# lora-rx.net
KiCad netlist of a schematic drawn in EAGLE
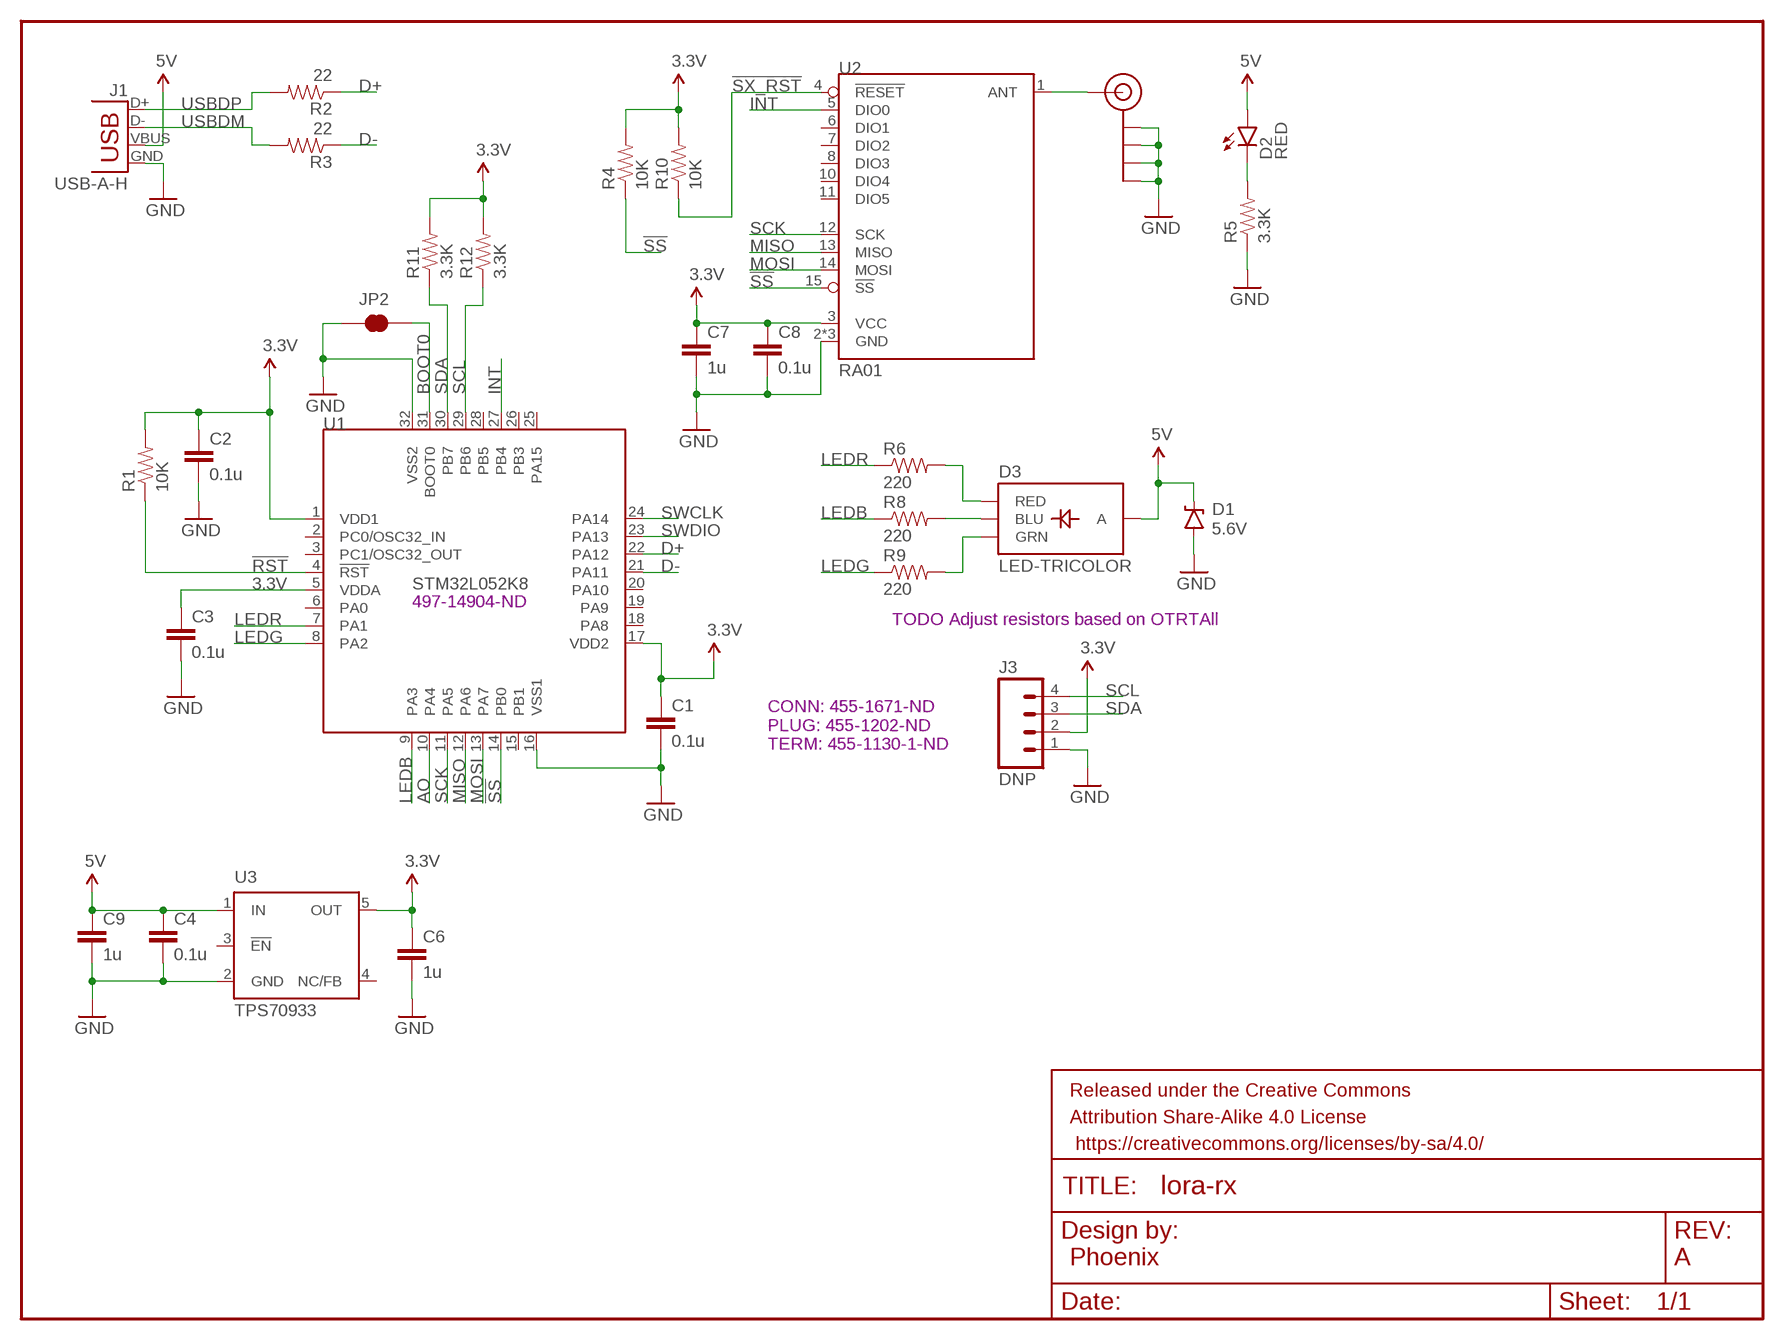
[diagram p0: schematic, sheet 1]

(export (version "E")
  (design (tool "Eeschema 10.0.6"))
  (components
    (comp (ref "C1")
      (value "0.1u")
      (footprint "eagle-import:0805")
      (libsource (lib "eagle-import") (part "CAP0805"))
    )
    (comp (ref "C2")
      (value "0.1u")
      (footprint "eagle-import:0805")
      (libsource (lib "eagle-import") (part "CAP0805"))
    )
    (comp (ref "C3")
      (value "0.1u")
      (footprint "eagle-import:0805")
      (libsource (lib "eagle-import") (part "CAP0805"))
    )
    (comp (ref "C4")
      (value "0.1u")
      (footprint "eagle-import:0805")
      (libsource (lib "eagle-import") (part "CAP0805"))
    )
    (comp (ref "C6")
      (value "1u")
      (footprint "eagle-import:0805")
      (libsource (lib "eagle-import") (part "CAP0805"))
    )
    (comp (ref "C7")
      (value "1u")
      (footprint "eagle-import:0805")
      (libsource (lib "eagle-import") (part "CAP0805"))
    )
    (comp (ref "C8")
      (value "0.1u")
      (footprint "eagle-import:0805")
      (libsource (lib "eagle-import") (part "CAP0805"))
    )
    (comp (ref "C9")
      (value "1u")
      (footprint "eagle-import:0805")
      (libsource (lib "eagle-import") (part "CAP0805"))
    )
    (comp (ref "D1")
      (value "5.6V")
      (footprint "eagle-import:SOD-323")
      (libsource (lib "eagle-import") (part "DIODE-ZENER5.6V"))
    )
    (comp (ref "D2")
      (value "RED")
      (footprint "eagle-import:LED-0603")
      (libsource (lib "eagle-import") (part "LED-RED0603"))
    )
    (comp (ref "D3")
      (value "LED-TRICOLOR")
      (footprint "eagle-import:LED-TRICOLOR-SMD")
      (libsource (lib "eagle-import") (part "LED-TRICOLOR"))
    )
    (comp (ref "FRAME1")
      (value "FRAME-LETTERNO_PACKAGE")
      (footprint "eagle-import:DUMMY")
      (fields (field (name "DESIGNER") "Nobody"))
      (libsource (lib "eagle-import") (part "FRAME-LETTERNO_PACKAGE"))
    )
    (comp (ref "J1")
      (value "USB-A-H")
      (footprint "eagle-import:USB-A-H")
      (libsource (lib "eagle-import") (part "USB-A-H"))
    )
    (comp (ref "J2")
      (value "SMA_EDGE")
      (footprint "eagle-import:SMA-EDGE")
      (libsource (lib "eagle-import") (part "SMA_EDGE"))
    )
    (comp (ref "J3")
      (value "DNP")
      (footprint "eagle-import:1X04-1.5MM_JST")
      (libsource (lib "eagle-import") (part "M04JST"))
    )
    (comp (ref "JP2")
      (value "JUMPER-SMT_2_NC_TRACE_NO-SILK")
      (footprint "eagle-import:SMT-JUMPER_2_NC_TRACE_NO-SILK")
      (libsource (lib "eagle-import") (part "JUMPER-SMT_2_NC_TRACE_NO-SILK"))
    )
    (comp (ref "R1")
      (value "10K")
      (footprint "eagle-import:0805")
      (libsource (lib "eagle-import") (part "RESISTOR0805-RES"))
    )
    (comp (ref "R2")
      (value "22")
      (footprint "eagle-import:0805")
      (libsource (lib "eagle-import") (part "RESISTOR0805-RES"))
    )
    (comp (ref "R3")
      (value "22")
      (footprint "eagle-import:0805")
      (libsource (lib "eagle-import") (part "RESISTOR0805-RES"))
    )
    (comp (ref "R4")
      (value "10K")
      (footprint "eagle-import:0805")
      (libsource (lib "eagle-import") (part "RESISTOR0805-RES"))
    )
    (comp (ref "R5")
      (value "3.3K")
      (footprint "eagle-import:0805")
      (libsource (lib "eagle-import") (part "RESISTOR0805-RES"))
    )
    (comp (ref "R6")
      (value "220")
      (footprint "eagle-import:0805")
      (libsource (lib "eagle-import") (part "RESISTOR0805-RES"))
    )
    (comp (ref "R8")
      (value "220")
      (footprint "eagle-import:0805")
      (libsource (lib "eagle-import") (part "RESISTOR0805-RES"))
    )
    (comp (ref "R9")
      (value "220")
      (footprint "eagle-import:0805")
      (libsource (lib "eagle-import") (part "RESISTOR0805-RES"))
    )
    (comp (ref "R10")
      (value "10K")
      (footprint "eagle-import:0805")
      (libsource (lib "eagle-import") (part "RESISTOR0805-RES"))
    )
    (comp (ref "R11")
      (value "3.3K")
      (footprint "eagle-import:0805")
      (libsource (lib "eagle-import") (part "RESISTOR0805-RES"))
    )
    (comp (ref "R12")
      (value "3.3K")
      (footprint "eagle-import:0805")
      (libsource (lib "eagle-import") (part "RESISTOR0805-RES"))
    )
    (comp (ref "U1")
      (value "STM32L052K8")
      (footprint "eagle-import:TQFP32-08")
      (libsource (lib "eagle-import") (part "STM32L05K"))
    )
    (comp (ref "U2")
      (value "RA01")
      (footprint "eagle-import:RA01")
      (libsource (lib "eagle-import") (part "RA01"))
    )
    (comp (ref "U3")
      (value "TPS70933")
      (footprint "eagle-import:SOT23-DBV")
      (fields (field (name "MF") "TEXAS INSTRUMENTS") (field (name "MPN") "TPS77033DBVT"))
      (libsource (lib "eagle-import") (part "TPS77033"))
    )
  )
  (nets
    (net (code "1") (name "/AO") (class "Default")
      (node (ref "U1") (pin "10") (pinfunction "PA4_10") (pintype "bidirectional"))
    )
    (net (code "2") (name "/BOOT0") (class "Default")
      (node (ref "JP2") (pin "2") (pinfunction "2_2") (pintype "passive"))
      (node (ref "U1") (pin "31") (pinfunction "BOOT0_31") (pintype "input"))
    )
    (net (code "3") (name "/D+") (class "Default")
      (node (ref "R2") (pin "1") (pinfunction "1_1") (pintype "passive"))
      (node (ref "U1") (pin "22") (pinfunction "PA12_22") (pintype "bidirectional"))
    )
    (net (code "4") (name "/D-") (class "Default")
      (node (ref "R3") (pin "1") (pinfunction "1_1") (pintype "passive"))
      (node (ref "U1") (pin "21") (pinfunction "PA11_21") (pintype "bidirectional"))
    )
    (net (code "5") (name "/INT") (class "Default")
      (node (ref "U1") (pin "27") (pinfunction "PB4_27") (pintype "bidirectional"))
      (node (ref "U2") (pin "5") (pinfunction "DIO0_5") (pintype "bidirectional"))
    )
    (net (code "6") (name "/LEDB") (class "Default")
      (node (ref "R8") (pin "1") (pinfunction "1_1") (pintype "passive"))
      (node (ref "U1") (pin "9") (pinfunction "PA3_9") (pintype "bidirectional"))
    )
    (net (code "7") (name "/LEDG") (class "Default")
      (node (ref "R9") (pin "1") (pinfunction "1_1") (pintype "passive"))
      (node (ref "U1") (pin "8") (pinfunction "PA2_8") (pintype "bidirectional"))
    )
    (net (code "8") (name "/LEDR") (class "Default")
      (node (ref "R6") (pin "1") (pinfunction "1_1") (pintype "passive"))
      (node (ref "U1") (pin "7") (pinfunction "PA1_7") (pintype "bidirectional"))
    )
    (net (code "9") (name "/MISO") (class "Default")
      (node (ref "U1") (pin "12") (pinfunction "PA6_12") (pintype "bidirectional"))
      (node (ref "U2") (pin "13") (pinfunction "MISO_13") (pintype "output"))
    )
    (net (code "10") (name "/MOSI") (class "Default")
      (node (ref "U1") (pin "13") (pinfunction "PA7_13") (pintype "bidirectional"))
      (node (ref "U2") (pin "14") (pinfunction "MOSI_14") (pintype "input"))
    )
    (net (code "11") (name "/SCK") (class "Default")
      (node (ref "U1") (pin "11") (pinfunction "PA5_11") (pintype "bidirectional"))
      (node (ref "U2") (pin "12") (pinfunction "SCK_12") (pintype "input"))
    )
    (net (code "12") (name "/SCL") (class "Default")
      (node (ref "J3") (pin "4") (pinfunction "4_4") (pintype "passive"))
      (node (ref "R12") (pin "1") (pinfunction "1_1") (pintype "passive"))
      (node (ref "U1") (pin "29") (pinfunction "PB6_29") (pintype "bidirectional"))
    )
    (net (code "13") (name "/SDA") (class "Default")
      (node (ref "J3") (pin "3") (pinfunction "3_3") (pintype "passive"))
      (node (ref "R11") (pin "1") (pinfunction "1_1") (pintype "passive"))
      (node (ref "U1") (pin "30") (pinfunction "PB7_30") (pintype "bidirectional"))
    )
    (net (code "14") (name "/SWCLK") (class "Default")
      (node (ref "U1") (pin "24") (pinfunction "PA14_24") (pintype "bidirectional"))
    )
    (net (code "15") (name "/SWDIO") (class "Default")
      (node (ref "U1") (pin "23") (pinfunction "PA13_23") (pintype "bidirectional"))
    )
    (net (code "16") (name "/USBDM") (class "Default")
      (node (ref "J1") (pin "D-") (pinfunction "D-_D-") (pintype "bidirectional"))
      (node (ref "R3") (pin "2") (pinfunction "2_2") (pintype "passive"))
    )
    (net (code "17") (name "/USBDP") (class "Default")
      (node (ref "J1") (pin "D+") (pinfunction "D+_D+") (pintype "bidirectional"))
      (node (ref "R2") (pin "2") (pinfunction "2_2") (pintype "passive"))
    )
    (net (code "18") (name "/~{RST}") (class "Default")
      (node (ref "R1") (pin "1") (pinfunction "1_1") (pintype "passive"))
      (node (ref "U1") (pin "4") (pinfunction "~{RST}_4") (pintype "input"))
    )
    (net (code "19") (name "/~{SS}") (class "Default")
      (node (ref "R4") (pin "1") (pinfunction "1_1") (pintype "passive"))
      (node (ref "U1") (pin "14") (pinfunction "PB0_14") (pintype "bidirectional"))
      (node (ref "U2") (pin "15") (pinfunction "~{SS}_15") (pintype "input"))
    )
    (net (code "20") (name "/~{SX_RST}") (class "Default")
      (node (ref "R10") (pin "1") (pinfunction "1_1") (pintype "passive"))
      (node (ref "U2") (pin "4") (pinfunction "~{RESET}_4") (pintype "input"))
    )
    (net (code "21") (name "3.3V") (class "Default")
      (node (ref "C1") (pin "1") (pinfunction "1_1") (pintype "passive"))
      (node (ref "C2") (pin "1") (pinfunction "1_1") (pintype "passive"))
      (node (ref "C3") (pin "1") (pinfunction "1_1") (pintype "passive"))
      (node (ref "C6") (pin "1") (pinfunction "1_1") (pintype "passive"))
      (node (ref "C7") (pin "1") (pinfunction "1_1") (pintype "passive"))
      (node (ref "C8") (pin "1") (pinfunction "1_1") (pintype "passive"))
      (node (ref "J3") (pin "2") (pinfunction "2_2") (pintype "passive"))
      (node (ref "R1") (pin "2") (pinfunction "2_2") (pintype "passive"))
      (node (ref "R10") (pin "2") (pinfunction "2_2") (pintype "passive"))
      (node (ref "R11") (pin "2") (pinfunction "2_2") (pintype "passive"))
      (node (ref "R12") (pin "2") (pinfunction "2_2") (pintype "passive"))
      (node (ref "R4") (pin "2") (pinfunction "2_2") (pintype "passive"))
      (node (ref "U1") (pin "1") (pinfunction "VDD1_1") (pintype "power_in"))
      (node (ref "U1") (pin "17") (pinfunction "VDD2_17") (pintype "power_in"))
      (node (ref "U1") (pin "5") (pinfunction "VDDA_5") (pintype "power_in"))
      (node (ref "U2") (pin "3") (pinfunction "VCC_3") (pintype "power_in"))
      (node (ref "U3") (pin "5") (pinfunction "OUT_5") (pintype "passive"))
    )
    (net (code "22") (name "5V") (class "Default")
      (node (ref "C4") (pin "1") (pinfunction "1_1") (pintype "passive"))
      (node (ref "C9") (pin "1") (pinfunction "1_1") (pintype "passive"))
      (node (ref "D1") (pin "C") (pinfunction "C_C") (pintype "passive"))
      (node (ref "D2") (pin "A") (pinfunction "A_A") (pintype "passive"))
      (node (ref "D3") (pin "A") (pinfunction "A_A") (pintype "bidirectional"))
      (node (ref "J1") (pin "VBUS") (pinfunction "VBUS_VBUS") (pintype "bidirectional"))
      (node (ref "U3") (pin "1") (pinfunction "IN_1") (pintype "input"))
    )
    (net (code "23") (name "GND") (class "Default")
      (node (ref "C1") (pin "2") (pinfunction "2_2") (pintype "passive"))
      (node (ref "C2") (pin "2") (pinfunction "2_2") (pintype "passive"))
      (node (ref "C3") (pin "2") (pinfunction "2_2") (pintype "passive"))
      (node (ref "C4") (pin "2") (pinfunction "2_2") (pintype "passive"))
      (node (ref "C6") (pin "2") (pinfunction "2_2") (pintype "passive"))
      (node (ref "C7") (pin "2") (pinfunction "2_2") (pintype "passive"))
      (node (ref "C8") (pin "2") (pinfunction "2_2") (pintype "passive"))
      (node (ref "C9") (pin "2") (pinfunction "2_2") (pintype "passive"))
      (node (ref "D1") (pin "A") (pinfunction "A_A") (pintype "passive"))
      (node (ref "J1") (pin "GND") (pinfunction "GND_GND") (pintype "bidirectional"))
      (node (ref "J2") (pin "GND@0") (pinfunction "GND_GND@0") (pintype "bidirectional"))
      (node (ref "J2") (pin "GND@1") (pinfunction "GND_GND@1") (pintype "bidirectional"))
      (node (ref "J2") (pin "GND@2") (pinfunction "GND_GND@2") (pintype "bidirectional"))
      (node (ref "J2") (pin "GND@3") (pinfunction "GND_GND@3") (pintype "bidirectional"))
      (node (ref "J3") (pin "1") (pinfunction "1_1") (pintype "passive"))
      (node (ref "JP2") (pin "1") (pinfunction "1_1") (pintype "passive"))
      (node (ref "R5") (pin "1") (pinfunction "1_1") (pintype "passive"))
      (node (ref "U1") (pin "16") (pinfunction "VSS1_16") (pintype "power_in"))
      (node (ref "U1") (pin "32") (pinfunction "VSS2_32") (pintype "power_in"))
      (node (ref "U2") (pin "16") (pinfunction "GND_16") (pintype "power_in"))
      (node (ref "U2") (pin "2") (pinfunction "GND_2") (pintype "power_in"))
      (node (ref "U2") (pin "9") (pinfunction "GND_9") (pintype "power_in"))
      (node (ref "U3") (pin "2") (pinfunction "GND_2") (pintype "power_in"))
    )
    (net (code "24") (name "Net-(D2-PadC)") (class "Default")
      (node (ref "D2") (pin "C") (pinfunction "C_C") (pintype "passive"))
      (node (ref "R5") (pin "2") (pinfunction "2_2") (pintype "passive"))
    )
    (net (code "25") (name "Net-(D3-BLU)") (class "Default")
      (node (ref "D3") (pin "B") (pinfunction "BLU_B") (pintype "bidirectional"))
      (node (ref "R8") (pin "2") (pinfunction "2_2") (pintype "passive"))
    )
    (net (code "26") (name "Net-(D3-GRN)") (class "Default")
      (node (ref "D3") (pin "G") (pinfunction "GRN_G") (pintype "bidirectional"))
      (node (ref "R9") (pin "2") (pinfunction "2_2") (pintype "passive"))
    )
    (net (code "27") (name "Net-(D3-RED)") (class "Default")
      (node (ref "D3") (pin "R") (pinfunction "RED_R") (pintype "bidirectional"))
      (node (ref "R6") (pin "2") (pinfunction "2_2") (pintype "passive"))
    )
    (net (code "28") (name "Net-(J2-SIGNAL)") (class "Default")
      (node (ref "J2") (pin "SIG") (pinfunction "SIGNAL_SIG") (pintype "bidirectional"))
      (node (ref "U2") (pin "1") (pinfunction "ANT_1") (pintype "passive"))
    )
    (net (code "29") (name "unconnected-(U1-PA0-Pad6)") (class "Default")
      (node (ref "U1") (pin "6") (pinfunction "PA0_6") (pintype "bidirectional"))
    )
    (net (code "30") (name "unconnected-(U1-PA8-Pad18)") (class "Default")
      (node (ref "U1") (pin "18") (pinfunction "PA8_18") (pintype "bidirectional"))
    )
    (net (code "31") (name "unconnected-(U1-PA9-Pad19)") (class "Default")
      (node (ref "U1") (pin "19") (pinfunction "PA9_19") (pintype "bidirectional"))
    )
    (net (code "32") (name "unconnected-(U1-PA10-Pad20)") (class "Default")
      (node (ref "U1") (pin "20") (pinfunction "PA10_20") (pintype "bidirectional"))
    )
    (net (code "33") (name "unconnected-(U1-PA15-Pad25)") (class "Default")
      (node (ref "U1") (pin "25") (pinfunction "PA15_25") (pintype "bidirectional"))
    )
    (net (code "34") (name "unconnected-(U1-PB1-Pad15)") (class "Default")
      (node (ref "U1") (pin "15") (pinfunction "PB1_15") (pintype "bidirectional"))
    )
    (net (code "35") (name "unconnected-(U1-PB3-Pad26)") (class "Default")
      (node (ref "U1") (pin "26") (pinfunction "PB3_26") (pintype "bidirectional"))
    )
    (net (code "36") (name "unconnected-(U1-PB5-Pad28)") (class "Default")
      (node (ref "U1") (pin "28") (pinfunction "PB5_28") (pintype "bidirectional"))
    )
    (net (code "37") (name "unconnected-(U1-PC0{slash}OSC32_IN-Pad2)") (class "Default")
      (node (ref "U1") (pin "2") (pinfunction "PC0/OSC32_IN_2") (pintype "bidirectional"))
    )
    (net (code "38") (name "unconnected-(U1-PC1{slash}OSC32_OUT-Pad3)") (class "Default")
      (node (ref "U1") (pin "3") (pinfunction "PC1/OSC32_OUT_3") (pintype "bidirectional"))
    )
    (net (code "39") (name "unconnected-(U2-DIO1-Pad6)") (class "Default")
      (node (ref "U2") (pin "6") (pinfunction "DIO1_6") (pintype "bidirectional"))
    )
    (net (code "40") (name "unconnected-(U2-DIO2-Pad7)") (class "Default")
      (node (ref "U2") (pin "7") (pinfunction "DIO2_7") (pintype "bidirectional"))
    )
    (net (code "41") (name "unconnected-(U2-DIO3-Pad8)") (class "Default")
      (node (ref "U2") (pin "8") (pinfunction "DIO3_8") (pintype "bidirectional"))
    )
    (net (code "42") (name "unconnected-(U2-DIO4-Pad10)") (class "Default")
      (node (ref "U2") (pin "10") (pinfunction "DIO4_10") (pintype "bidirectional"))
    )
    (net (code "43") (name "unconnected-(U2-DIO5-Pad11)") (class "Default")
      (node (ref "U2") (pin "11") (pinfunction "DIO5_11") (pintype "bidirectional"))
    )
    (net (code "44") (name "unconnected-(U3-NC{slash}FB-Pad4)") (class "Default")
      (node (ref "U3") (pin "4") (pinfunction "NC/FB_4") (pintype "passive"))
    )
    (net (code "45") (name "unconnected-(U3-~{EN}-Pad3)") (class "Default")
      (node (ref "U3") (pin "3") (pinfunction "~{EN}_3") (pintype "input"))
    )
  )
)
